# RH049_2.net
KiCad netlist of a schematic drawn in EAGLE
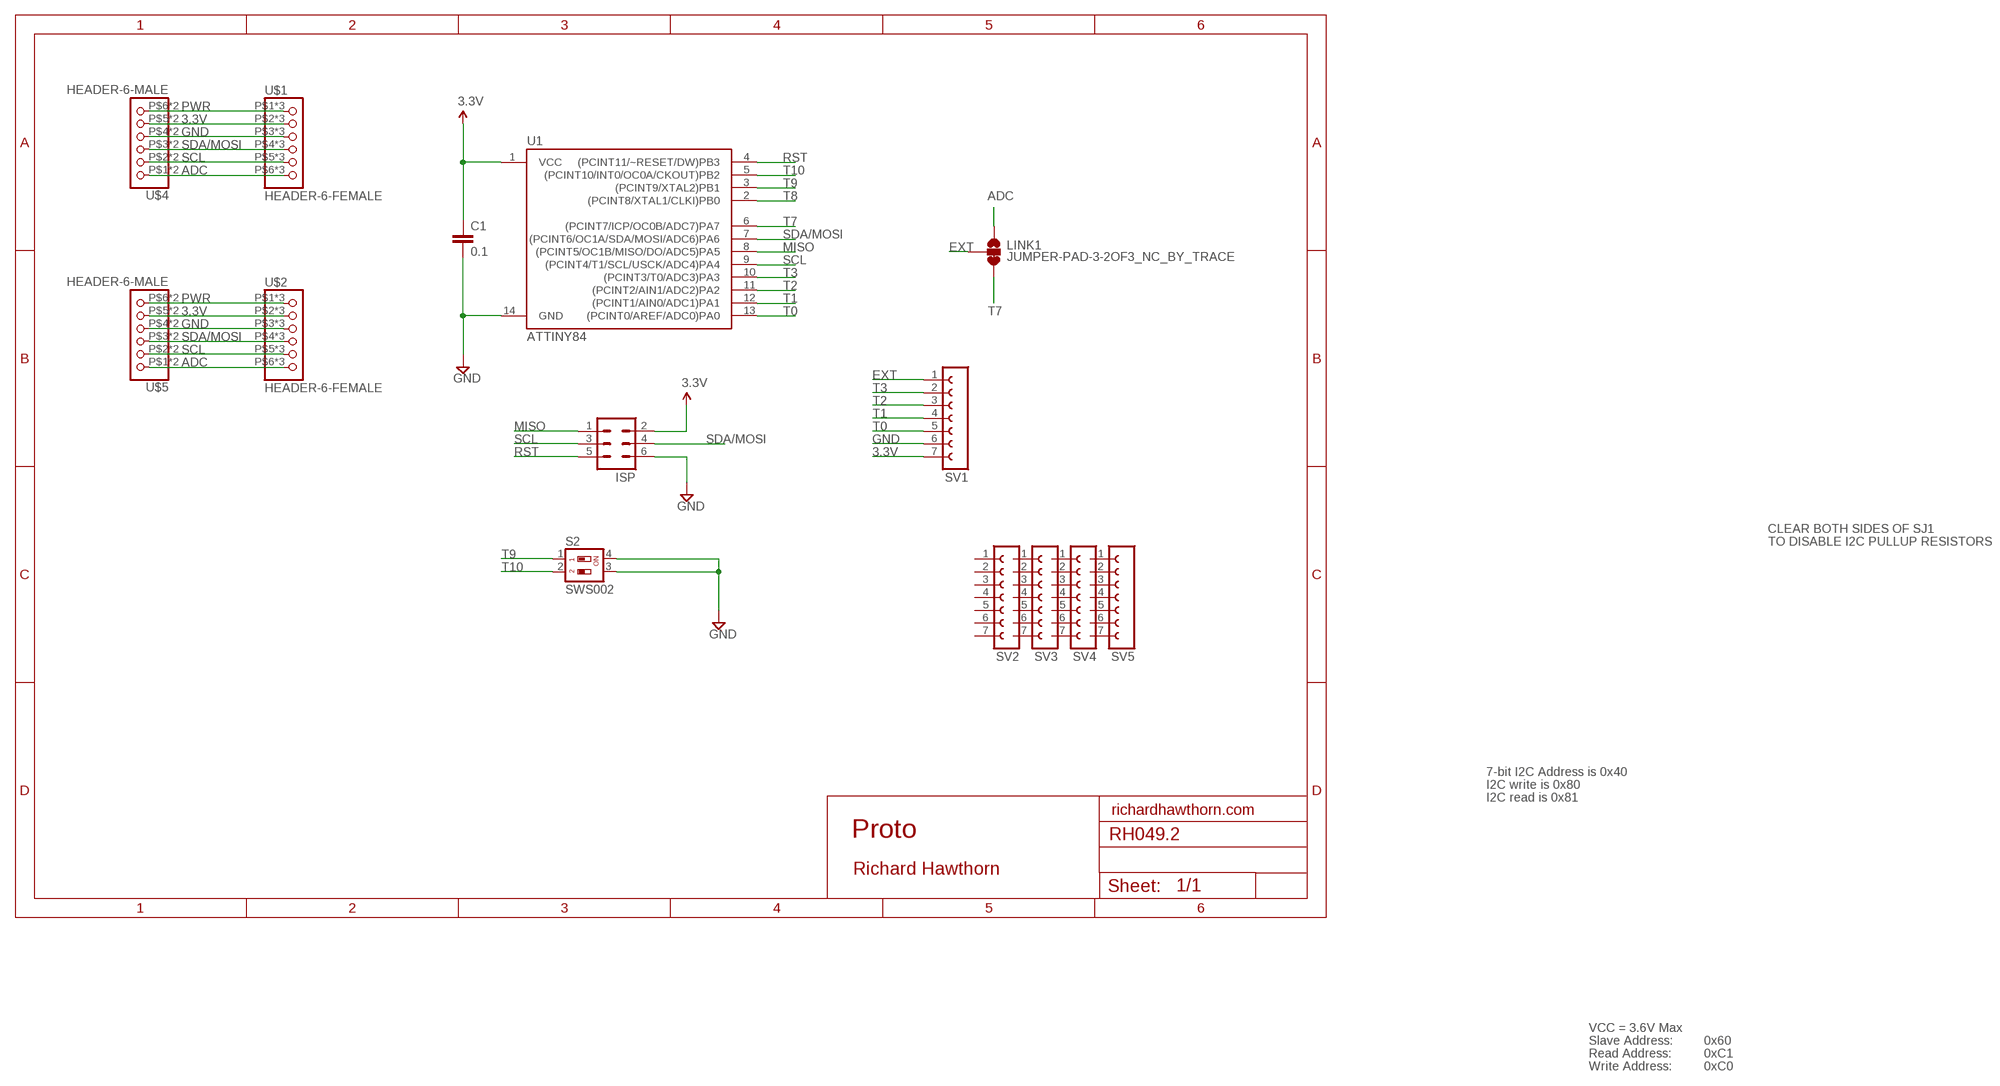
[diagram p0: schematic, sheet 1]

(export (version "E")
  (design (tool "Eeschema 10.0.6"))
  (components
    (comp (ref "C1")
      (value "0.1")
      (footprint "eagle-import:0603-CAP")
      (libsource (lib "eagle-import") (part "CAP0603-CAP"))
    )
    (comp (ref "ISP")
      (value "MA03-2")
      (footprint "eagle-import:MA03-2")
      (libsource (lib "eagle-import") (part "MA03-2"))
    )
    (comp (ref "LINK1")
      (value "JUMPER-PAD-3-2OF3_NC_BY_TRACE")
      (footprint "eagle-import:PAD-JUMPER-3-2OF3_NC_BY_TRACE_YES_SILK_FULL_BOX")
      (libsource (lib "eagle-import") (part "JUMPER-PAD-3-2OF3_NC_BY_TRACE"))
    )
    (comp (ref "S2")
      (value "SWS002")
      (footprint "eagle-import:SMS-002")
      (libsource (lib "eagle-import") (part "SWS002"))
    )
    (comp (ref "SV1")
      (value "FE07-1")
      (footprint "eagle-import:FE07")
      (libsource (lib "eagle-import") (part "FE07-1"))
    )
    (comp (ref "SV2")
      (value "FE07-1")
      (footprint "eagle-import:FE07")
      (libsource (lib "eagle-import") (part "FE07-1"))
    )
    (comp (ref "SV3")
      (value "FE07-1")
      (footprint "eagle-import:FE07")
      (libsource (lib "eagle-import") (part "FE07-1"))
    )
    (comp (ref "SV4")
      (value "FE07-1")
      (footprint "eagle-import:FE07")
      (libsource (lib "eagle-import") (part "FE07-1"))
    )
    (comp (ref "SV5")
      (value "FE07-1")
      (footprint "eagle-import:FE07")
      (libsource (lib "eagle-import") (part "FE07-1"))
    )
    (comp (ref "U$1")
      (value "HEADER-6-FEMALE")
      (footprint "eagle-import:2MMHEADER6")
      (libsource (lib "eagle-import") (part "HEADER-6-FEMALE"))
    )
    (comp (ref "U$2")
      (value "HEADER-6-FEMALE")
      (footprint "eagle-import:2MMHEADER6")
      (libsource (lib "eagle-import") (part "HEADER-6-FEMALE"))
    )
    (comp (ref "U$4")
      (value "HEADER-6-MALE")
      (footprint "eagle-import:2MMHEADERPIN6")
      (libsource (lib "eagle-import") (part "HEADER-6-MALE"))
    )
    (comp (ref "U$5")
      (value "HEADER-6-MALE")
      (footprint "eagle-import:2MMHEADERPIN6")
      (libsource (lib "eagle-import") (part "HEADER-6-MALE"))
    )
    (comp (ref "U1")
      (value "ATTINY84")
      (footprint "eagle-import:SO14")
      (libsource (lib "eagle-import") (part "ATTINY84"))
    )
  )
  (nets
    (net (code "1") (name "/ADC") (class "Default")
      (node (ref "LINK1") (pin "1") (pinfunction "1_1") (pintype "passive"))
      (node (ref "U$1") (pin "P$14") (pinfunction "6_P$14") (pintype "passive"))
      (node (ref "U$1") (pin "P$22") (pinfunction "6_P$22") (pintype "passive"))
      (node (ref "U$1") (pin "P$6") (pinfunction "6_P$6") (pintype "passive"))
      (node (ref "U$2") (pin "P$14") (pinfunction "6_P$14") (pintype "passive"))
      (node (ref "U$2") (pin "P$22") (pinfunction "6_P$22") (pintype "passive"))
      (node (ref "U$2") (pin "P$6") (pinfunction "6_P$6") (pintype "passive"))
      (node (ref "U$4") (pin "P$1") (pinfunction "1_P$1") (pintype "passive"))
      (node (ref "U$4") (pin "P$9") (pinfunction "1_P$9") (pintype "passive"))
      (node (ref "U$5") (pin "P$1") (pinfunction "1_P$1") (pintype "passive"))
      (node (ref "U$5") (pin "P$9") (pinfunction "1_P$9") (pintype "passive"))
    )
    (net (code "2") (name "/EXT") (class "Default")
      (node (ref "LINK1") (pin "2") (pinfunction "2_2") (pintype "passive"))
      (node (ref "SV1") (pin "1") (pinfunction "1_1") (pintype "passive"))
    )
    (net (code "3") (name "/MISO") (class "Default")
      (node (ref "ISP") (pin "1") (pinfunction "1_1") (pintype "passive"))
      (node (ref "U1") (pin "8") (pinfunction "(PCINT5/OC1B/MISO/DO/ADC5)PA5_8") (pintype "bidirectional"))
    )
    (net (code "4") (name "/PWR") (class "Default")
      (node (ref "U$1") (pin "P$1") (pinfunction "1_P$1") (pintype "passive"))
      (node (ref "U$1") (pin "P$17") (pinfunction "1_P$17") (pintype "passive"))
      (node (ref "U$1") (pin "P$9") (pinfunction "1_P$9") (pintype "passive"))
      (node (ref "U$2") (pin "P$1") (pinfunction "1_P$1") (pintype "passive"))
      (node (ref "U$2") (pin "P$17") (pinfunction "1_P$17") (pintype "passive"))
      (node (ref "U$2") (pin "P$9") (pinfunction "1_P$9") (pintype "passive"))
      (node (ref "U$4") (pin "P$14") (pinfunction "6_P$14") (pintype "passive"))
      (node (ref "U$4") (pin "P$6") (pinfunction "6_P$6") (pintype "passive"))
      (node (ref "U$5") (pin "P$14") (pinfunction "6_P$14") (pintype "passive"))
      (node (ref "U$5") (pin "P$6") (pinfunction "6_P$6") (pintype "passive"))
    )
    (net (code "5") (name "/RST") (class "Default")
      (node (ref "ISP") (pin "5") (pinfunction "5_5") (pintype "passive"))
      (node (ref "U1") (pin "4") (pinfunction "(PCINT11/~{RESET/DW})PB3_4") (pintype "bidirectional"))
    )
    (net (code "6") (name "/SCL") (class "Default")
      (node (ref "ISP") (pin "3") (pinfunction "3_3") (pintype "passive"))
      (node (ref "U$1") (pin "P$13") (pinfunction "5_P$13") (pintype "passive"))
      (node (ref "U$1") (pin "P$21") (pinfunction "5_P$21") (pintype "passive"))
      (node (ref "U$1") (pin "P$5") (pinfunction "5_P$5") (pintype "passive"))
      (node (ref "U$2") (pin "P$13") (pinfunction "5_P$13") (pintype "passive"))
      (node (ref "U$2") (pin "P$21") (pinfunction "5_P$21") (pintype "passive"))
      (node (ref "U$2") (pin "P$5") (pinfunction "5_P$5") (pintype "passive"))
      (node (ref "U$4") (pin "P$10") (pinfunction "2_P$10") (pintype "passive"))
      (node (ref "U$4") (pin "P$2") (pinfunction "2_P$2") (pintype "passive"))
      (node (ref "U$5") (pin "P$10") (pinfunction "2_P$10") (pintype "passive"))
      (node (ref "U$5") (pin "P$2") (pinfunction "2_P$2") (pintype "passive"))
      (node (ref "U1") (pin "9") (pinfunction "(PCINT4/T1/SCL/USCK/ADC4)PA4_9") (pintype "bidirectional"))
    )
    (net (code "7") (name "/SDA{slash}MOSI") (class "Default")
      (node (ref "ISP") (pin "4") (pinfunction "4_4") (pintype "passive"))
      (node (ref "U$1") (pin "P$12") (pinfunction "4_P$12") (pintype "passive"))
      (node (ref "U$1") (pin "P$20") (pinfunction "4_P$20") (pintype "passive"))
      (node (ref "U$1") (pin "P$4") (pinfunction "4_P$4") (pintype "passive"))
      (node (ref "U$2") (pin "P$12") (pinfunction "4_P$12") (pintype "passive"))
      (node (ref "U$2") (pin "P$20") (pinfunction "4_P$20") (pintype "passive"))
      (node (ref "U$2") (pin "P$4") (pinfunction "4_P$4") (pintype "passive"))
      (node (ref "U$4") (pin "P$11") (pinfunction "3_P$11") (pintype "passive"))
      (node (ref "U$4") (pin "P$3") (pinfunction "3_P$3") (pintype "passive"))
      (node (ref "U$5") (pin "P$11") (pinfunction "3_P$11") (pintype "passive"))
      (node (ref "U$5") (pin "P$3") (pinfunction "3_P$3") (pintype "passive"))
      (node (ref "U1") (pin "7") (pinfunction "(PCINT6/OC1A/SDA/MOSI/ADC6)PA6_7") (pintype "bidirectional"))
    )
    (net (code "8") (name "/T0") (class "Default")
      (node (ref "SV1") (pin "5") (pinfunction "5_5") (pintype "passive"))
      (node (ref "U1") (pin "13") (pinfunction "(PCINT0/AREF/ADC0)PA0_13") (pintype "bidirectional"))
    )
    (net (code "9") (name "/T1") (class "Default")
      (node (ref "SV1") (pin "4") (pinfunction "4_4") (pintype "passive"))
      (node (ref "U1") (pin "12") (pinfunction "(PCINT1/AIN0/ADC1)PA1_12") (pintype "bidirectional"))
    )
    (net (code "10") (name "/T2") (class "Default")
      (node (ref "SV1") (pin "3") (pinfunction "3_3") (pintype "passive"))
      (node (ref "U1") (pin "11") (pinfunction "(PCINT2/AIN1/ADC2)PA2_11") (pintype "bidirectional"))
    )
    (net (code "11") (name "/T3") (class "Default")
      (node (ref "SV1") (pin "2") (pinfunction "2_2") (pintype "passive"))
      (node (ref "U1") (pin "10") (pinfunction "(PCINT3/T0/ADC3)PA3_10") (pintype "bidirectional"))
    )
    (net (code "12") (name "/T7") (class "Default")
      (node (ref "LINK1") (pin "3") (pinfunction "3_3") (pintype "passive"))
      (node (ref "U1") (pin "6") (pinfunction "(PCINT7/ICP/OC0B/ADC7)PA7_6") (pintype "bidirectional"))
    )
    (net (code "13") (name "/T8") (class "Default")
      (node (ref "U1") (pin "2") (pinfunction "(PCINT8/XTAL1/CLKI)PB0_2") (pintype "bidirectional"))
    )
    (net (code "14") (name "/T9") (class "Default")
      (node (ref "S2") (pin "1") (pinfunction "1_1") (pintype "passive"))
      (node (ref "U1") (pin "3") (pinfunction "(PCINT9/XTAL2)PB1_3") (pintype "bidirectional"))
    )
    (net (code "15") (name "/T10") (class "Default")
      (node (ref "S2") (pin "2") (pinfunction "2_2") (pintype "passive"))
      (node (ref "U1") (pin "5") (pinfunction "(PCINT10/INT0/OC0A/CKOUT)PB2_5") (pintype "bidirectional"))
    )
    (net (code "16") (name "3.3V") (class "Default")
      (node (ref "C1") (pin "1") (pinfunction "1_1") (pintype "passive"))
      (node (ref "ISP") (pin "2") (pinfunction "2_2") (pintype "passive"))
      (node (ref "SV1") (pin "7") (pinfunction "7_7") (pintype "passive"))
      (node (ref "U$1") (pin "P$10") (pinfunction "2_P$10") (pintype "passive"))
      (node (ref "U$1") (pin "P$18") (pinfunction "2_P$18") (pintype "passive"))
      (node (ref "U$1") (pin "P$2") (pinfunction "2_P$2") (pintype "passive"))
      (node (ref "U$2") (pin "P$10") (pinfunction "2_P$10") (pintype "passive"))
      (node (ref "U$2") (pin "P$18") (pinfunction "2_P$18") (pintype "passive"))
      (node (ref "U$2") (pin "P$2") (pinfunction "2_P$2") (pintype "passive"))
      (node (ref "U$4") (pin "P$13") (pinfunction "5_P$13") (pintype "passive"))
      (node (ref "U$4") (pin "P$5") (pinfunction "5_P$5") (pintype "passive"))
      (node (ref "U$5") (pin "P$13") (pinfunction "5_P$13") (pintype "passive"))
      (node (ref "U$5") (pin "P$5") (pinfunction "5_P$5") (pintype "passive"))
      (node (ref "U1") (pin "1") (pinfunction "VCC_1") (pintype "bidirectional"))
    )
    (net (code "17") (name "GND") (class "Default")
      (node (ref "C1") (pin "2") (pinfunction "2_2") (pintype "passive"))
      (node (ref "ISP") (pin "6") (pinfunction "6_6") (pintype "passive"))
      (node (ref "S2") (pin "3") (pinfunction "3_3") (pintype "passive"))
      (node (ref "S2") (pin "4") (pinfunction "4_4") (pintype "passive"))
      (node (ref "SV1") (pin "6") (pinfunction "6_6") (pintype "passive"))
      (node (ref "U$1") (pin "P$11") (pinfunction "3_P$11") (pintype "passive"))
      (node (ref "U$1") (pin "P$19") (pinfunction "3_P$19") (pintype "passive"))
      (node (ref "U$1") (pin "P$3") (pinfunction "3_P$3") (pintype "passive"))
      (node (ref "U$2") (pin "P$11") (pinfunction "3_P$11") (pintype "passive"))
      (node (ref "U$2") (pin "P$19") (pinfunction "3_P$19") (pintype "passive"))
      (node (ref "U$2") (pin "P$3") (pinfunction "3_P$3") (pintype "passive"))
      (node (ref "U$4") (pin "P$12") (pinfunction "4_P$12") (pintype "passive"))
      (node (ref "U$4") (pin "P$4") (pinfunction "4_P$4") (pintype "passive"))
      (node (ref "U$5") (pin "P$12") (pinfunction "4_P$12") (pintype "passive"))
      (node (ref "U$5") (pin "P$4") (pinfunction "4_P$4") (pintype "passive"))
      (node (ref "U1") (pin "14") (pinfunction "GND_14") (pintype "bidirectional"))
    )
    (net (code "18") (name "unconnected-(SV2-Pad1)") (class "Default")
      (node (ref "SV2") (pin "1") (pinfunction "1_1") (pintype "passive"))
    )
    (net (code "19") (name "unconnected-(SV2-Pad2)") (class "Default")
      (node (ref "SV2") (pin "2") (pinfunction "2_2") (pintype "passive"))
    )
    (net (code "20") (name "unconnected-(SV2-Pad3)") (class "Default")
      (node (ref "SV2") (pin "3") (pinfunction "3_3") (pintype "passive"))
    )
    (net (code "21") (name "unconnected-(SV2-Pad4)") (class "Default")
      (node (ref "SV2") (pin "4") (pinfunction "4_4") (pintype "passive"))
    )
    (net (code "22") (name "unconnected-(SV2-Pad5)") (class "Default")
      (node (ref "SV2") (pin "5") (pinfunction "5_5") (pintype "passive"))
    )
    (net (code "23") (name "unconnected-(SV2-Pad6)") (class "Default")
      (node (ref "SV2") (pin "6") (pinfunction "6_6") (pintype "passive"))
    )
    (net (code "24") (name "unconnected-(SV2-Pad7)") (class "Default")
      (node (ref "SV2") (pin "7") (pinfunction "7_7") (pintype "passive"))
    )
    (net (code "25") (name "unconnected-(SV3-Pad1)") (class "Default")
      (node (ref "SV3") (pin "1") (pinfunction "1_1") (pintype "passive"))
    )
    (net (code "26") (name "unconnected-(SV3-Pad2)") (class "Default")
      (node (ref "SV3") (pin "2") (pinfunction "2_2") (pintype "passive"))
    )
    (net (code "27") (name "unconnected-(SV3-Pad3)") (class "Default")
      (node (ref "SV3") (pin "3") (pinfunction "3_3") (pintype "passive"))
    )
    (net (code "28") (name "unconnected-(SV3-Pad4)") (class "Default")
      (node (ref "SV3") (pin "4") (pinfunction "4_4") (pintype "passive"))
    )
    (net (code "29") (name "unconnected-(SV3-Pad5)") (class "Default")
      (node (ref "SV3") (pin "5") (pinfunction "5_5") (pintype "passive"))
    )
    (net (code "30") (name "unconnected-(SV3-Pad6)") (class "Default")
      (node (ref "SV3") (pin "6") (pinfunction "6_6") (pintype "passive"))
    )
    (net (code "31") (name "unconnected-(SV3-Pad7)") (class "Default")
      (node (ref "SV3") (pin "7") (pinfunction "7_7") (pintype "passive"))
    )
    (net (code "32") (name "unconnected-(SV4-Pad1)") (class "Default")
      (node (ref "SV4") (pin "1") (pinfunction "1_1") (pintype "passive"))
    )
    (net (code "33") (name "unconnected-(SV4-Pad2)") (class "Default")
      (node (ref "SV4") (pin "2") (pinfunction "2_2") (pintype "passive"))
    )
    (net (code "34") (name "unconnected-(SV4-Pad3)") (class "Default")
      (node (ref "SV4") (pin "3") (pinfunction "3_3") (pintype "passive"))
    )
    (net (code "35") (name "unconnected-(SV4-Pad4)") (class "Default")
      (node (ref "SV4") (pin "4") (pinfunction "4_4") (pintype "passive"))
    )
    (net (code "36") (name "unconnected-(SV4-Pad5)") (class "Default")
      (node (ref "SV4") (pin "5") (pinfunction "5_5") (pintype "passive"))
    )
    (net (code "37") (name "unconnected-(SV4-Pad6)") (class "Default")
      (node (ref "SV4") (pin "6") (pinfunction "6_6") (pintype "passive"))
    )
    (net (code "38") (name "unconnected-(SV4-Pad7)") (class "Default")
      (node (ref "SV4") (pin "7") (pinfunction "7_7") (pintype "passive"))
    )
    (net (code "39") (name "unconnected-(SV5-Pad1)") (class "Default")
      (node (ref "SV5") (pin "1") (pinfunction "1_1") (pintype "passive"))
    )
    (net (code "40") (name "unconnected-(SV5-Pad2)") (class "Default")
      (node (ref "SV5") (pin "2") (pinfunction "2_2") (pintype "passive"))
    )
    (net (code "41") (name "unconnected-(SV5-Pad3)") (class "Default")
      (node (ref "SV5") (pin "3") (pinfunction "3_3") (pintype "passive"))
    )
    (net (code "42") (name "unconnected-(SV5-Pad4)") (class "Default")
      (node (ref "SV5") (pin "4") (pinfunction "4_4") (pintype "passive"))
    )
    (net (code "43") (name "unconnected-(SV5-Pad5)") (class "Default")
      (node (ref "SV5") (pin "5") (pinfunction "5_5") (pintype "passive"))
    )
    (net (code "44") (name "unconnected-(SV5-Pad6)") (class "Default")
      (node (ref "SV5") (pin "6") (pinfunction "6_6") (pintype "passive"))
    )
    (net (code "45") (name "unconnected-(SV5-Pad7)") (class "Default")
      (node (ref "SV5") (pin "7") (pinfunction "7_7") (pintype "passive"))
    )
  )
)
